# HLK-LD-KIT-V2_0.net
KiCad netlist of a schematic drawn in Altium Designer
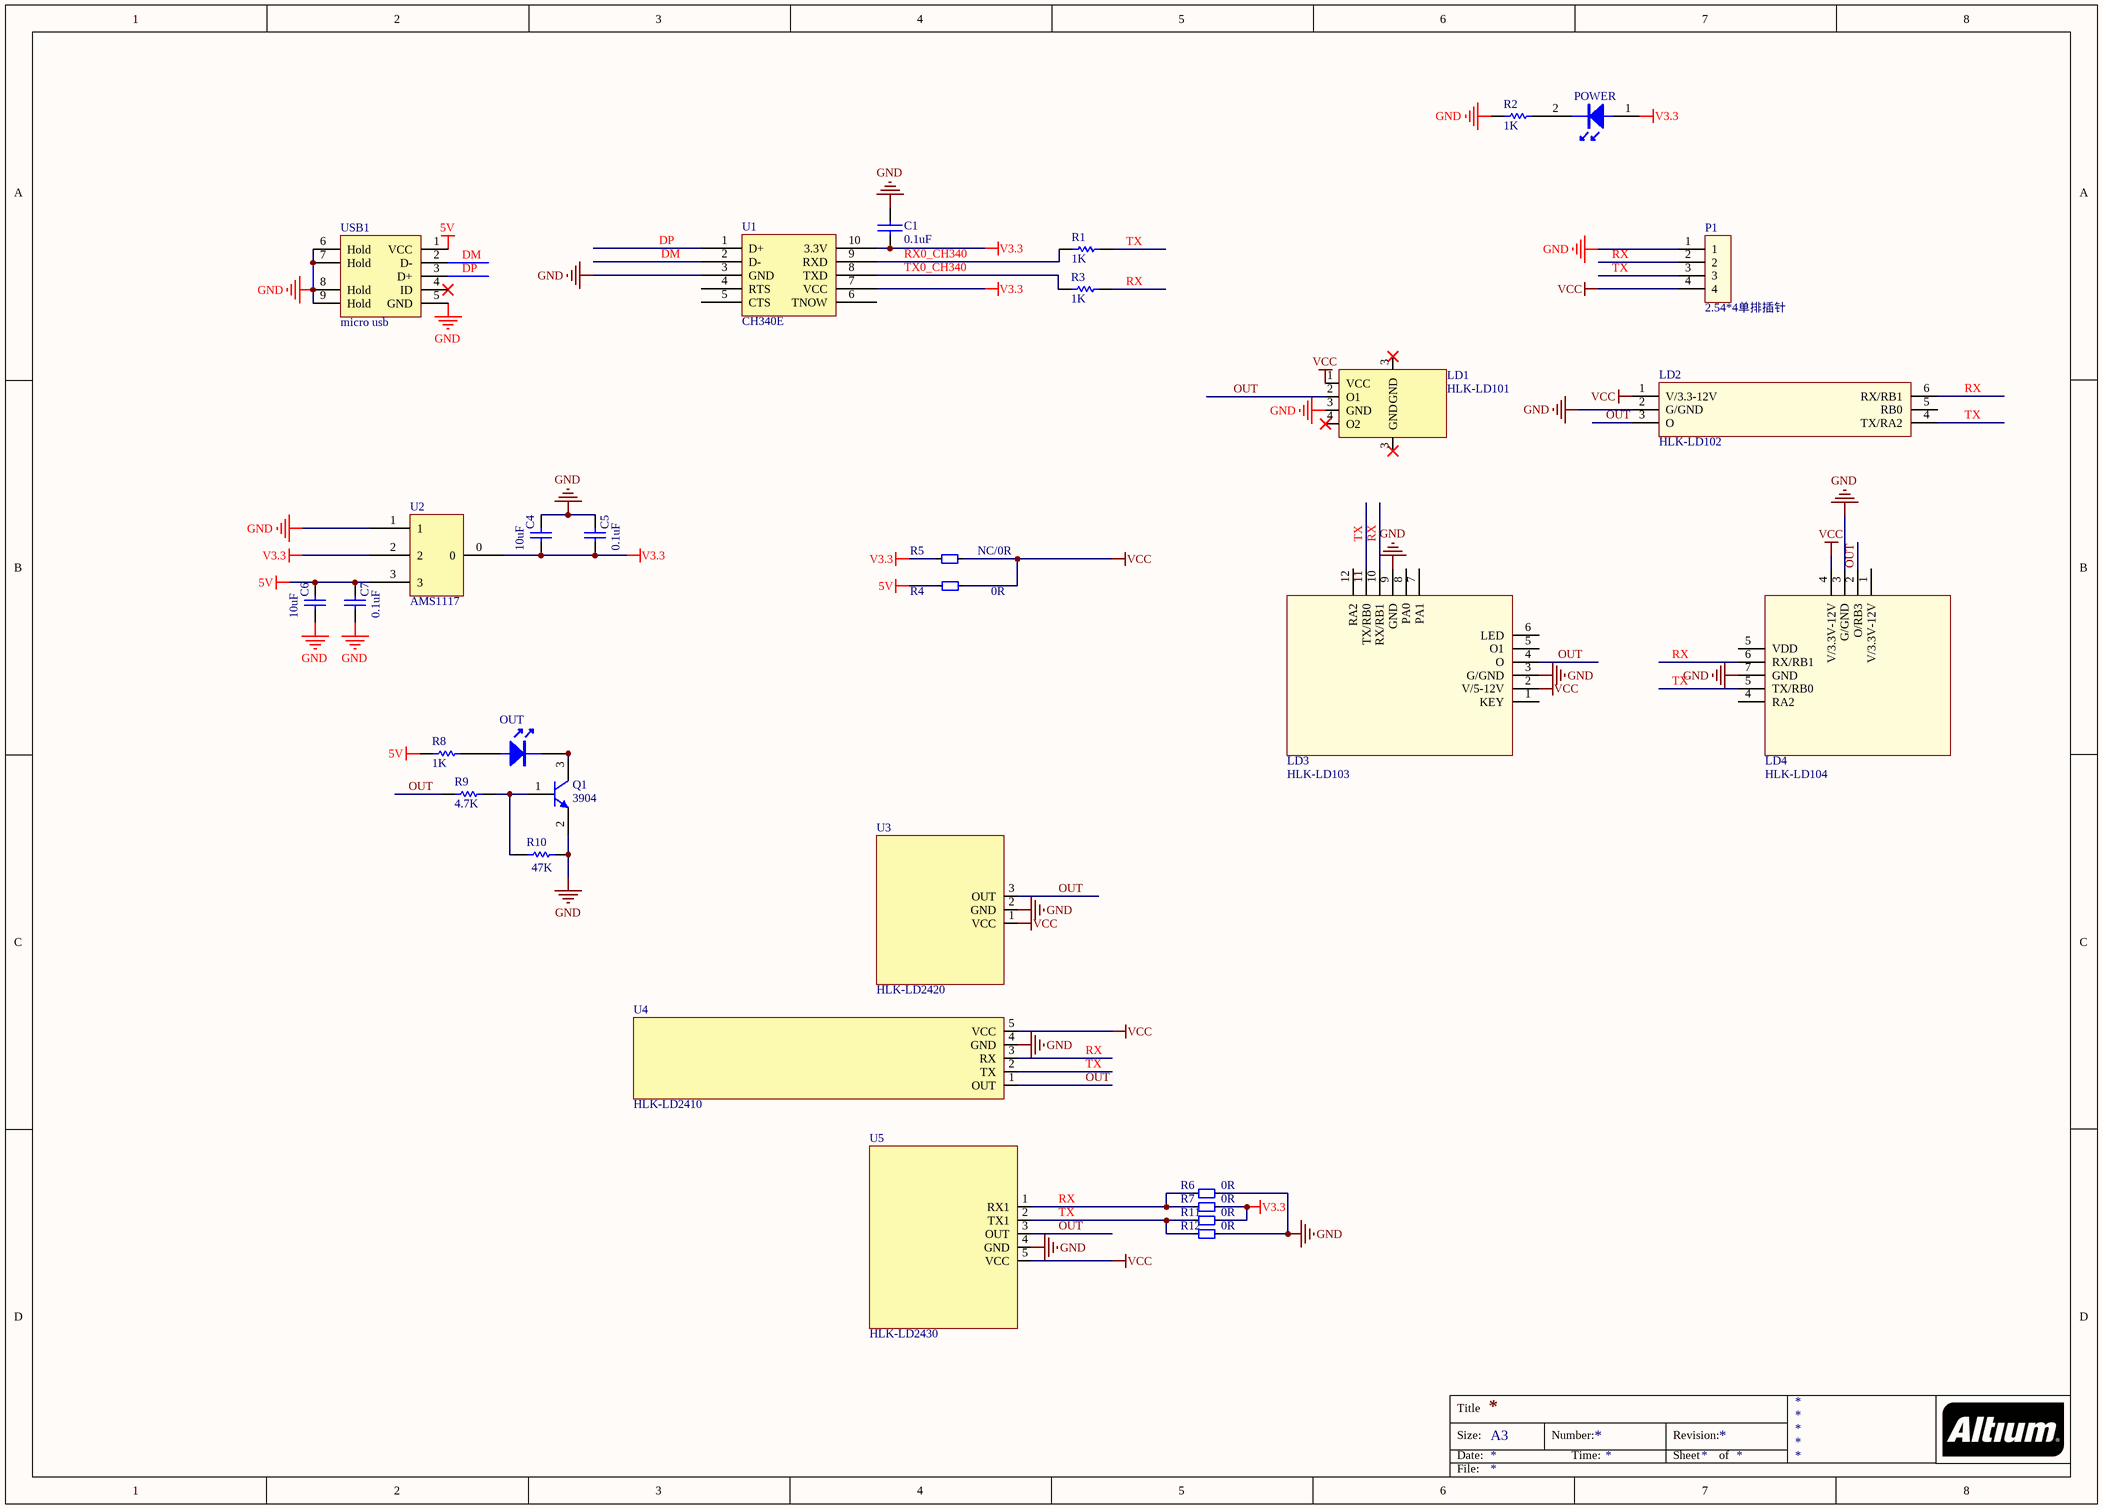
[diagram p0: HLK-LD-KIT-V2.0.SchDoc]

(export (version "E")
  (design (tool "Eeschema 10.0.6"))
  (components
    (comp (ref "C1")
      (value "0.1uF")
      (footprint "0603")
      (description "Capacitor")
      (libsource (lib "*") (part "CAP"))
    )
    (comp (ref "C4")
      (value "10uF")
      (footprint "0603")
      (description "Capacitor")
      (fields (field (name "PUBLISHER") "Altium Limited"))
      (libsource (lib "Miscellaneous Devices") (part "Cap"))
    )
    (comp (ref "C5")
      (value "0.1uF")
      (footprint "0603")
      (description "Capacitor")
      (fields (field (name "PUBLISHER") "Altium Limited"))
      (libsource (lib "Miscellaneous Devices") (part "Cap"))
    )
    (comp (ref "C6")
      (value "10uF")
      (footprint "0603")
      (description "Capacitor")
      (fields (field (name "PUBLISHER") "Altium Limited"))
      (libsource (lib "Miscellaneous Devices") (part "Cap"))
    )
    (comp (ref "C7")
      (value "0.1uF")
      (footprint "0603")
      (description "Capacitor")
      (fields (field (name "PUBLISHER") "Altium Limited"))
      (libsource (lib "Miscellaneous Devices") (part "Cap"))
    )
    (comp (ref "LD1") (value "HLK-LD101") (footprint "LD101") (libsource (lib "Schlib1") (part "LD101")))
    (comp (ref "LD2") (value "HLK-LD102") (footprint "LD102") (libsource (lib "") (part "HLK-LD015-5G_2")))
    (comp (ref "LD3") (value "HLK-LD103") (footprint "LD103") (libsource (lib "") (part "HLK-LD015-5G_1")))
    (comp (ref "LD4")
      (value "HLK-LD104")
      (footprint "LD104")
      (libsource (lib "Schlib1") (part "HLK-LD015-5G"))
    )
    (comp (ref "OUT")
      (value "~")
      (footprint "0603LED")
      (libsource (lib "Miscellaneous Devices") (part "LED"))
    )
    (comp (ref "P1")
      (value "2.54*4单排插针")
      (footprint "SIP_4P_2.54")
      (libsource (lib "Schlib1") (part "2.54*2插针"))
    )
    (comp (ref "POWER") (value "LED") (footprint "0603LED") (libsource (lib "") (part "LED_1")))
    (comp (ref "Q1")
      (value "3904")
      (footprint "SOT-23")
      (description "NPN General Purpose Amplifier")
      (fields (field (name "PUBLISHER") "Altium Limited"))
      (libsource (lib "PCB_Project1") (part "A09T"))
    )
    (comp (ref "R1")
      (value "1K")
      (footprint "0603")
      (description "Resistor")
      (fields (field (name "PUBLISHER") "Altium Limited"))
      (libsource (lib "Miscellaneous Devices") (part "Res1"))
    )
    (comp (ref "R2")
      (value "1K")
      (footprint "0603")
      (description "Resistor")
      (fields (field (name "PUBLISHER") "Altium Limited"))
      (libsource (lib "Miscellaneous Devices") (part "Res1"))
    )
    (comp (ref "R3")
      (value "1K")
      (footprint "0603")
      (description "Resistor")
      (fields (field (name "PUBLISHER") "Altium Limited"))
      (libsource (lib "Miscellaneous Devices") (part "Res1"))
    )
    (comp (ref "R4") (value "0R") (footprint "R0603") (libsource (lib "jerry") (part "R")))
    (comp (ref "R5") (value "NC/0R") (footprint "R0603") (libsource (lib "jerry") (part "R")))
    (comp (ref "R6") (value "0R") (footprint "R0603") (libsource (lib "jerry") (part "R")))
    (comp (ref "R7") (value "0R") (footprint "R0603") (libsource (lib "jerry") (part "R")))
    (comp (ref "R8")
      (value "1K")
      (footprint "0603")
      (description "Resistor")
      (fields (field (name "PUBLISHER") "Altium Limited"))
      (libsource (lib "Miscellaneous Devices") (part "Res1"))
    )
    (comp (ref "R9")
      (value "4.7K")
      (footprint "0603")
      (description "Resistor")
      (fields (field (name "PUBLISHER") "Altium Limited"))
      (libsource (lib "Miscellaneous Devices") (part "Res1"))
    )
    (comp (ref "R10")
      (value "47K")
      (footprint "0603")
      (description "Resistor")
      (fields (field (name "PUBLISHER") "Altium Limited"))
      (libsource (lib "Miscellaneous Devices") (part "Res1"))
    )
    (comp (ref "R11") (value "0R") (footprint "R0603") (libsource (lib "jerry") (part "R")))
    (comp (ref "R12") (value "0R") (footprint "R0603") (libsource (lib "jerry") (part "R")))
    (comp (ref "U1") (value "CH340E") (footprint "MSOP-10") (libsource (lib "Schlib1") (part "CH340E")))
    (comp (ref "U2") (value "AMS1117") (footprint "1117") (libsource (lib "Schlib1") (part "Component_1")))
    (comp (ref "U3")
      (value "HLK-LD2420")
      (footprint "HLK-LD2420")
      (description "生命存在24G雷达")
      (libsource (lib "13.1 - 模块") (part "HLK-LD2420"))
    )
    (comp (ref "U4")
      (value "HLK-LD2410")
      (footprint "HLK-LD2410")
      (description "生命存在24G雷达")
      (libsource (lib "13.1 - 模块") (part "HLK-LD2410"))
    )
    (comp (ref "U5")
      (value "HLK-LD2430")
      (footprint "HLK-LD2430")
      (description "生命存在24G雷达")
      (libsource (lib "13.1 - 模块") (part "HLK-LD2430"))
    )
    (comp (ref "USB1")
      (value "micro usb")
      (footprint "USB-MICRO_D")
      (libsource (lib "HLK-N10-KIT-V1.0") (part "USB-D"))
    )
  )
  (nets
    (net (code "1") (name "/DM") (class "Default")
      (node (ref "U1") (pin "2") (pinfunction "D-_2") (pintype "passive"))
      (node (ref "USB1") (pin "2") (pinfunction "D-_2") (pintype "passive"))
    )
    (net (code "2") (name "/DP") (class "Default")
      (node (ref "U1") (pin "1") (pinfunction "D+_1") (pintype "passive"))
      (node (ref "USB1") (pin "3") (pinfunction "D+_3") (pintype "passive"))
    )
    (net (code "3") (name "/OUT") (class "Default")
      (node (ref "LD1") (pin "2") (pinfunction "O1_2") (pintype "passive"))
      (node (ref "LD2") (pin "3") (pinfunction "O_3") (pintype "passive"))
      (node (ref "LD3") (pin "4") (pinfunction "O_4") (pintype "passive"))
      (node (ref "LD4") (pin "2") (pinfunction "O/RB3_2") (pintype "passive"))
      (node (ref "R9") (pin "2") (pinfunction "2_2") (pintype "passive"))
      (node (ref "U3") (pin "3") (pinfunction "OUT_3") (pintype "passive"))
      (node (ref "U4") (pin "1") (pinfunction "OUT_1") (pintype "passive"))
      (node (ref "U5") (pin "3") (pinfunction "OUT_3") (pintype "passive"))
    )
    (net (code "4") (name "/RX") (class "Default")
      (node (ref "LD2") (pin "6") (pinfunction "RX/RB1_6") (pintype "passive"))
      (node (ref "LD3") (pin "10") (pinfunction "RX/RB1_10") (pintype "passive"))
      (node (ref "LD4") (pin "6") (pinfunction "RX/RB1_6") (pintype "passive"))
      (node (ref "P1") (pin "2") (pinfunction "2_2") (pintype "passive"))
      (node (ref "R3") (pin "1") (pinfunction "1_1") (pintype "passive"))
      (node (ref "R6") (pin "2") (pinfunction "2_2") (pintype "passive"))
      (node (ref "R7") (pin "2") (pinfunction "2_2") (pintype "passive"))
      (node (ref "U4") (pin "3") (pinfunction "RX_3") (pintype "passive"))
      (node (ref "U5") (pin "1") (pinfunction "RX1_1") (pintype "passive"))
    )
    (net (code "5") (name "/RX0_CH340") (class "Default")
      (node (ref "R1") (pin "2") (pinfunction "2_2") (pintype "passive"))
      (node (ref "U1") (pin "9") (pinfunction "RXD_9") (pintype "passive"))
    )
    (net (code "6") (name "/TX") (class "Default")
      (node (ref "LD2") (pin "4") (pinfunction "TX/RA2_4") (pintype "passive"))
      (node (ref "LD3") (pin "11") (pinfunction "TX/RB0_11") (pintype "passive"))
      (node (ref "LD4") (pin "5") (pinfunction "TX/RB0_5") (pintype "passive"))
      (node (ref "P1") (pin "3") (pinfunction "3_3") (pintype "passive"))
      (node (ref "R1") (pin "1") (pinfunction "1_1") (pintype "passive"))
      (node (ref "R11") (pin "2") (pinfunction "2_2") (pintype "passive"))
      (node (ref "R12") (pin "2") (pinfunction "2_2") (pintype "passive"))
      (node (ref "U4") (pin "2") (pinfunction "TX_2") (pintype "passive"))
      (node (ref "U5") (pin "2") (pinfunction "TX1_2") (pintype "passive"))
    )
    (net (code "7") (name "/TX0_CH340") (class "Default")
      (node (ref "R3") (pin "2") (pinfunction "2_2") (pintype "passive"))
      (node (ref "U1") (pin "8") (pinfunction "TXD_8") (pintype "passive"))
    )
    (net (code "8") (name "5V") (class "Default")
      (node (ref "C6") (pin "1") (pinfunction "1_1") (pintype "passive"))
      (node (ref "C7") (pin "1") (pinfunction "1_1") (pintype "passive"))
      (node (ref "R4") (pin "2") (pinfunction "2_2") (pintype "passive"))
      (node (ref "R8") (pin "1") (pinfunction "1_1") (pintype "passive"))
      (node (ref "U2") (pin "3") (pinfunction "3_3") (pintype "passive"))
      (node (ref "USB1") (pin "1") (pinfunction "VCC_1") (pintype "passive"))
    )
    (net (code "9") (name "GND") (class "Default")
      (node (ref "C1") (pin "1") (pinfunction "1_1") (pintype "passive"))
      (node (ref "C4") (pin "1") (pinfunction "1_1") (pintype "passive"))
      (node (ref "C5") (pin "1") (pinfunction "1_1") (pintype "passive"))
      (node (ref "C6") (pin "2") (pinfunction "2_2") (pintype "passive"))
      (node (ref "C7") (pin "2") (pinfunction "2_2") (pintype "passive"))
      (node (ref "LD1") (pin "3") (pinfunction "GND_3") (pintype "passive"))
      (node (ref "LD2") (pin "2") (pinfunction "G/GND_2") (pintype "passive"))
      (node (ref "LD3") (pin "3") (pinfunction "G/GND_3") (pintype "passive"))
      (node (ref "LD3") (pin "9") (pinfunction "GND_9") (pintype "passive"))
      (node (ref "LD4") (pin "3") (pinfunction "G/GND_3") (pintype "passive"))
      (node (ref "LD4") (pin "7") (pinfunction "GND_7") (pintype "passive"))
      (node (ref "P1") (pin "1") (pinfunction "1_1") (pintype "passive"))
      (node (ref "Q1") (pin "2") (pinfunction "E_2") (pintype "passive"))
      (node (ref "R10") (pin "1") (pinfunction "1_1") (pintype "passive"))
      (node (ref "R12") (pin "1") (pinfunction "1_1") (pintype "passive"))
      (node (ref "R2") (pin "2") (pinfunction "2_2") (pintype "passive"))
      (node (ref "R6") (pin "1") (pinfunction "1_1") (pintype "passive"))
      (node (ref "U1") (pin "3") (pinfunction "GND_3") (pintype "passive"))
      (node (ref "U2") (pin "1") (pinfunction "1_1") (pintype "passive"))
      (node (ref "U3") (pin "2") (pinfunction "GND_2") (pintype "passive"))
      (node (ref "U4") (pin "4") (pinfunction "GND_4") (pintype "passive"))
      (node (ref "U5") (pin "4") (pinfunction "GND_4") (pintype "passive"))
      (node (ref "USB1") (pin "5") (pinfunction "GND_5") (pintype "passive"))
      (node (ref "USB1") (pin "6") (pinfunction "Hold_6") (pintype "passive"))
      (node (ref "USB1") (pin "7") (pinfunction "Hold_7") (pintype "passive"))
      (node (ref "USB1") (pin "8") (pinfunction "Hold_8") (pintype "passive"))
      (node (ref "USB1") (pin "9") (pinfunction "Hold_9") (pintype "passive"))
    )
    (net (code "10") (name "Net-(OUT-Pad1)") (class "Default")
      (node (ref "OUT") (pin "1") (pinfunction "1_1") (pintype "passive"))
      (node (ref "R8") (pin "2") (pinfunction "2_2") (pintype "passive"))
    )
    (net (code "11") (name "Net-(POWER-Pad2)") (class "Default")
      (node (ref "POWER") (pin "2") (pinfunction "2_2") (pintype "passive"))
      (node (ref "R2") (pin "1") (pinfunction "1_1") (pintype "passive"))
    )
    (net (code "12") (name "Net-(Q1-B)") (class "Default")
      (node (ref "Q1") (pin "1") (pinfunction "B_1") (pintype "passive"))
      (node (ref "R10") (pin "2") (pinfunction "2_2") (pintype "passive"))
      (node (ref "R9") (pin "1") (pinfunction "1_1") (pintype "passive"))
    )
    (net (code "13") (name "Net-(Q1-C)") (class "Default")
      (node (ref "OUT") (pin "2") (pinfunction "2_2") (pintype "passive"))
      (node (ref "Q1") (pin "3") (pinfunction "C_3") (pintype "passive"))
    )
    (net (code "14") (name "V3.3") (class "Default")
      (node (ref "C1") (pin "2") (pinfunction "2_2") (pintype "passive"))
      (node (ref "C4") (pin "2") (pinfunction "2_2") (pintype "passive"))
      (node (ref "C5") (pin "2") (pinfunction "2_2") (pintype "passive"))
      (node (ref "POWER") (pin "1") (pinfunction "1_1") (pintype "passive"))
      (node (ref "R11") (pin "1") (pinfunction "1_1") (pintype "passive"))
      (node (ref "R5") (pin "2") (pinfunction "2_2") (pintype "passive"))
      (node (ref "R7") (pin "1") (pinfunction "1_1") (pintype "passive"))
      (node (ref "U1") (pin "10") (pinfunction "3.3V_10") (pintype "passive"))
      (node (ref "U1") (pin "7") (pinfunction "VCC_7") (pintype "passive"))
      (node (ref "U2") (pin "0") (pinfunction "0_0") (pintype "passive"))
      (node (ref "U2") (pin "2") (pinfunction "2_2") (pintype "passive"))
    )
    (net (code "15") (name "VCC") (class "Default")
      (node (ref "LD1") (pin "1") (pinfunction "VCC_1") (pintype "passive"))
      (node (ref "LD2") (pin "1") (pinfunction "V/3.3-12V_1") (pintype "passive"))
      (node (ref "LD3") (pin "2") (pinfunction "V/5-12V_2") (pintype "passive"))
      (node (ref "LD4") (pin "4") (pinfunction "V/3.3V-12V_4") (pintype "passive"))
      (node (ref "P1") (pin "4") (pinfunction "4_4") (pintype "passive"))
      (node (ref "R4") (pin "1") (pinfunction "1_1") (pintype "passive"))
      (node (ref "R5") (pin "1") (pinfunction "1_1") (pintype "passive"))
      (node (ref "U3") (pin "1") (pinfunction "VCC_1") (pintype "passive"))
      (node (ref "U4") (pin "5") (pinfunction "VCC_5") (pintype "passive"))
      (node (ref "U5") (pin "5") (pinfunction "VCC_5") (pintype "passive"))
    )
    (net (code "16") (name "unconnected-(LD1-GND-Pad3)") (class "Default")
      (node (ref "LD1") (pin "3") (pinfunction "GND_3") (pintype "passive+no_connect"))
    )
    (net (code "17") (name "unconnected-(LD1-GND-Pad3)_1") (class "Default")
      (node (ref "LD1") (pin "3") (pinfunction "GND_3") (pintype "passive+no_connect"))
    )
    (net (code "18") (name "unconnected-(LD1-O2-Pad4)") (class "Default")
      (node (ref "LD1") (pin "4") (pinfunction "O2_4") (pintype "passive+no_connect"))
    )
    (net (code "19") (name "unconnected-(LD2-RB0-Pad5)") (class "Default")
      (node (ref "LD2") (pin "5") (pinfunction "RB0_5") (pintype "passive"))
    )
    (net (code "20") (name "unconnected-(LD3-KEY-Pad1)") (class "Default")
      (node (ref "LD3") (pin "1") (pinfunction "KEY_1") (pintype "passive"))
    )
    (net (code "21") (name "unconnected-(LD3-LED-Pad6)") (class "Default")
      (node (ref "LD3") (pin "6") (pinfunction "LED_6") (pintype "passive"))
    )
    (net (code "22") (name "unconnected-(LD3-O1-Pad5)") (class "Default")
      (node (ref "LD3") (pin "5") (pinfunction "O1_5") (pintype "passive"))
    )
    (net (code "23") (name "unconnected-(LD3-PA0-Pad8)") (class "Default")
      (node (ref "LD3") (pin "8") (pinfunction "PA0_8") (pintype "passive"))
    )
    (net (code "24") (name "unconnected-(LD3-PA1-Pad7)") (class "Default")
      (node (ref "LD3") (pin "7") (pinfunction "PA1_7") (pintype "passive"))
    )
    (net (code "25") (name "unconnected-(LD3-RA2-Pad12)") (class "Default")
      (node (ref "LD3") (pin "12") (pinfunction "RA2_12") (pintype "passive"))
    )
    (net (code "26") (name "unconnected-(LD4-RA2-Pad4)") (class "Default")
      (node (ref "LD4") (pin "4") (pinfunction "RA2_4") (pintype "passive"))
    )
    (net (code "27") (name "unconnected-(LD4-VDD-Pad5)") (class "Default")
      (node (ref "LD4") (pin "5") (pinfunction "VDD_5") (pintype "passive"))
    )
    (net (code "28") (name "unconnected-(LD4-V{slash}3.3V-12V-Pad1)") (class "Default")
      (node (ref "LD4") (pin "1") (pinfunction "V/3.3V-12V_1") (pintype "passive"))
    )
    (net (code "29") (name "unconnected-(U1-CTS-Pad5)") (class "Default")
      (node (ref "U1") (pin "5") (pinfunction "CTS_5") (pintype "passive"))
    )
    (net (code "30") (name "unconnected-(U1-RTS-Pad4)") (class "Default")
      (node (ref "U1") (pin "4") (pinfunction "RTS_4") (pintype "passive"))
    )
    (net (code "31") (name "unconnected-(U1-TNOW-Pad6)") (class "Default")
      (node (ref "U1") (pin "6") (pinfunction "TNOW_6") (pintype "passive"))
    )
    (net (code "32") (name "unconnected-(USB1-ID-Pad4)") (class "Default")
      (node (ref "USB1") (pin "4") (pinfunction "ID_4") (pintype "passive+no_connect"))
    )
  )
)
